# power-management.net
KiCad netlist of a schematic drawn in Altium Designer
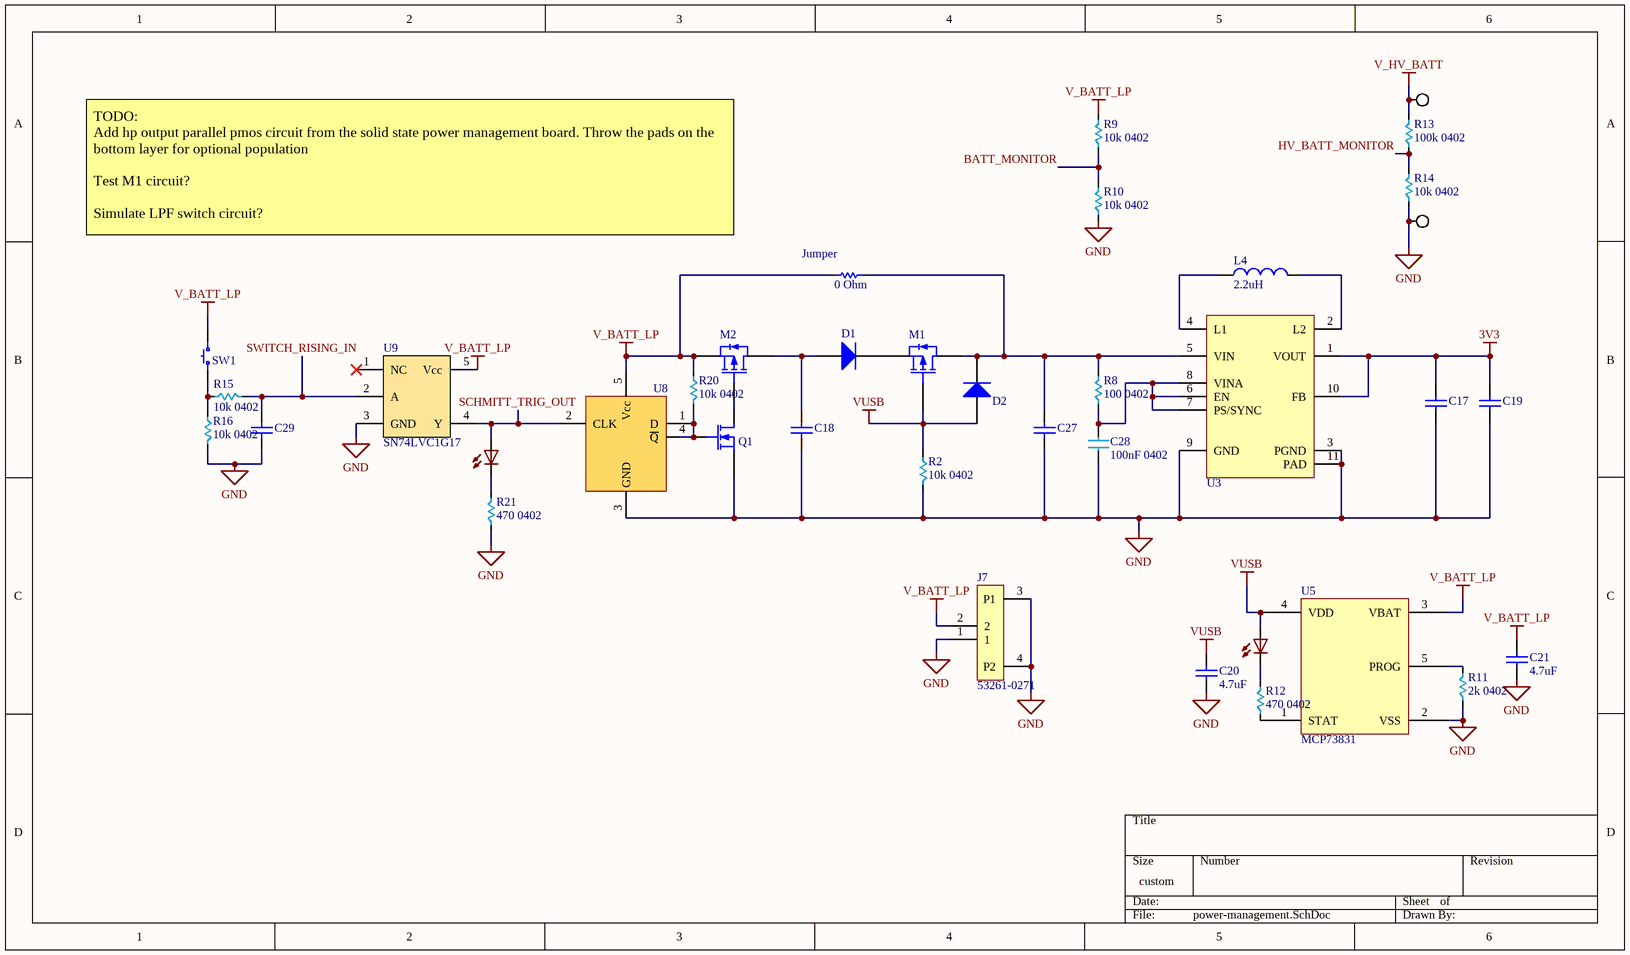
[diagram p0: power-management.SchDoc]

(export (version "E")
  (design (tool "Eeschema 10.0.6"))
  (components
    (comp (ref "0 Ohm")
      (value "Jumper")
      (footprint "0805-1")
      (fields
        (field (name "MANUFACTURER") "Panasonic")
        (field (name "MANUFACTURER PART NUMBER") "ERJ-6LWJR007V")
        (field (name "TOLERANCE") "5%")
      )
      (libsource (lib "robot-cortex") (part "R-0-0805"))
    )
    (comp (ref "C17")
      (value "10uF 0603")
      (footprint "C0603")
      (libsource (lib "robot-cortex") (part "C-10.0uF-0603"))
    )
    (comp (ref "C18")
      (value "10uF 0603")
      (footprint "C0603")
      (libsource (lib "robot-cortex") (part "C-10.0uF-0603"))
    )
    (comp (ref "C19")
      (value "10uF 0603")
      (footprint "C0603")
      (libsource (lib "robot-cortex") (part "C-10.0uF-0603"))
    )
    (comp (ref "C20")
      (value "4.7uF")
      (footprint "C0603")
      (description "4.7uF 0603")
      (fields
        (field (name "MANUFACTURER") "Samsung")
        (field (name "MANUFACTURER PART NUMBER") "CL05F104ZO5NNNC")
        (field (name "PUBLISHER") "Altium Limited")
      )
      (libsource (lib "robot-cortex") (part "C-4.7uF-0603"))
    )
    (comp (ref "C21")
      (value "4.7uF")
      (footprint "C0603")
      (description "4.7uF 0603")
      (fields
        (field (name "MANUFACTURER") "Samsung")
        (field (name "MANUFACTURER PART NUMBER") "CL05F104ZO5NNNC")
        (field (name "PUBLISHER") "Altium Limited")
      )
      (libsource (lib "robot-cortex") (part "C-4.7uF-0603"))
    )
    (comp (ref "C27")
      (value "10uF 0603")
      (footprint "C0603")
      (libsource (lib "robot-cortex") (part "C-10.0uF-0603"))
    )
    (comp (ref "C28") (value "100nF 0402") (footprint "C0402") (libsource (lib "RLC") (part "C0402-100nF")))
    (comp (ref "C29")
      (value "10uF 0603")
      (footprint "C0603")
      (libsource (lib "robot-cortex") (part "C-10.0uF-0603"))
    )
    (comp (ref "D1")
      (value "NSR0530HT1G")
      (footprint "SOD-323")
      (description "DIODE SCHOTTKY 30V 500MA SOD323")
      (fields (field (name "MANUFACTURER") "ON Semiconductor"))
      (libsource (lib "robot-cortex") (part "NSR0530HT1G"))
    )
    (comp (ref "D2")
      (value "NSR0530HT1G")
      (footprint "SOD-323")
      (description "DIODE SCHOTTKY 30V 500MA SOD323")
      (fields (field (name "MANUFACTURER") "ON Semiconductor"))
      (libsource (lib "robot-cortex") (part "NSR0530HT1G"))
    )
    (comp (ref "J7")
      (value "53261-0271")
      (footprint "0532610271")
      (description "Headers & Wire Housings 1.25MM HDR 2 CKT Right-Angle")
      (fields (field (name "MANUFACTURER") "Molex"))
      (libsource (lib "robot-cortex") (part "53261-0271"))
    )
    (comp (ref "J18")
      (value "PAD-SINGLE")
      (footprint "PAD-SINGLE")
      (description "Single Thru Hole Pad")
      (libsource (lib "robot-cortex") (part "PAD-SINGLE"))
    )
    (comp (ref "J19")
      (value "PAD-SINGLE")
      (footprint "PAD-SINGLE")
      (description "Single Thru Hole Pad")
      (libsource (lib "robot-cortex") (part "PAD-SINGLE"))
    )
    (comp (ref "L4")
      (value "2.2uH")
      (footprint "L1210")
      (description "2.2uH 1210")
      (libsource (lib "robot-cortex") (part "DFE322520FD-2R2M=P2"))
    )
    (comp (ref "LED3")
      (value "LED WHITE 0603")
      (footprint "LED_0603")
      (description "LED   Source: http://www.osram.convergy.de   Source: www.luxeon.com   Source: www.kingbright.com")
      (fields
        (field (name "MANUFACTURER") "Dialight")
        (field (name "MANUFACTURER PART NUMBER") "5988070107F")
      )
      (libsource (lib "robot-cortex") (part "LED_ESML0603"))
    )
    (comp (ref "LED4")
      (value "LED WHITE 0603")
      (footprint "LED_0603")
      (description "LED   Source: http://www.osram.convergy.de   Source: www.luxeon.com   Source: www.kingbright.com")
      (fields
        (field (name "MANUFACTURER") "Dialight")
        (field (name "MANUFACTURER PART NUMBER") "5988070107F")
      )
      (libsource (lib "robot-cortex") (part "LED_ESML0603"))
    )
    (comp (ref "M1")
      (value "csd25402q3a")
      (footprint "SON65P330X90-8N")
      (libsource (lib "robot-cortex") (part "CSD25402Q3A"))
    )
    (comp (ref "M2")
      (value "csd25402q3a")
      (footprint "SON65P330X90-8N")
      (libsource (lib "robot-cortex") (part "CSD25402Q3A"))
    )
    (comp (ref "Q1")
      (value "n-mos low power")
      (footprint "SOT-23-3")
      (fields
        (field (name "MANUFACTURER") "ON Semiconductor / Fairchild")
        (field (name "MANUFACTURER PART NUMBER") "NDS351N")
      )
      (libsource (lib "robot-cortex") (part "NDS351N"))
    )
    (comp (ref "R2")
      (value "10k 0402")
      (footprint "R0402")
      (libsource (lib "robot-cortex") (part "R-10k-0402"))
    )
    (comp (ref "R8")
      (value "100 0402")
      (footprint "R0402")
      (libsource (lib "robot-cortex") (part "R-100-0402"))
    )
    (comp (ref "R9")
      (value "10k 0402")
      (footprint "R0402")
      (libsource (lib "robot-cortex") (part "R-10k-0402"))
    )
    (comp (ref "R10")
      (value "10k 0402")
      (footprint "R0402")
      (libsource (lib "robot-cortex") (part "R-10k-0402"))
    )
    (comp (ref "R11")
      (value "2k 0402")
      (footprint "R0402")
      (libsource (lib "robot-cortex") (part "R-2k-0402"))
    )
    (comp (ref "R12")
      (value "470 0402")
      (footprint "R0402")
      (fields
        (field (name "MANUFACTURER") "Yageo")
        (field (name "MANUFACTURER PART NUMBER") "RC0402JR-07470RL")
        (field (name "TOLERANCE") "5%")
      )
      (libsource (lib "robot-cortex") (part "R-470-0402"))
    )
    (comp (ref "R13")
      (value "100k 0402")
      (footprint "R0402")
      (libsource (lib "robot-cortex") (part "R-100k-0402"))
    )
    (comp (ref "R14")
      (value "10k 0402")
      (footprint "R0402")
      (libsource (lib "robot-cortex") (part "R-10k-0402"))
    )
    (comp (ref "R15")
      (value "10k 0402")
      (footprint "R0402")
      (libsource (lib "robot-cortex") (part "R-10k-0402"))
    )
    (comp (ref "R16")
      (value "10k 0402")
      (footprint "R0402")
      (libsource (lib "robot-cortex") (part "R-10k-0402"))
    )
    (comp (ref "R20")
      (value "10k 0402")
      (footprint "R0402")
      (libsource (lib "robot-cortex") (part "R-10k-0402"))
    )
    (comp (ref "R21")
      (value "470 0402")
      (footprint "R0402")
      (fields
        (field (name "MANUFACTURER") "Yageo")
        (field (name "MANUFACTURER PART NUMBER") "RC0402JR-07470RL")
        (field (name "TOLERANCE") "5%")
      )
      (libsource (lib "robot-cortex") (part "R-470-0402"))
    )
    (comp (ref "SW1")
      (value "EVQ-P7A01P")
      (footprint "EVQ-P7A01P")
      (description "SWITCH TACTILE SPST-NO 50MA 32V")
      (fields (field (name "MANUFACTURER") "ITT C&K") (field (name "MANUFACTURER PART NUMBER") "KMR742NGLFS"))
      (libsource (lib "robot-cortex") (part "EVQ-P7A01P"))
    )
    (comp (ref "U3")
      (value "TPS63001DRCR")
      (footprint "DRC0010J")
      (libsource (lib "robot-cortex") (part "TPS63001DRCR"))
    )
    (comp (ref "U5")
      (value "MCP73831")
      (footprint "SOT-23-5")
      (libsource (lib "robot-cortex") (part "MCP73831"))
    )
    (comp (ref "U8")
      (value "SN74LVC1G80DCK")
      (footprint "DCK-SC70-TI")
      (description "Flip Flop Inverted Output")
      (libsource (lib "robot-cortex") (part "SN74LVC1G80DCK"))
    )
    (comp (ref "U9")
      (value "SN74LVC1G17")
      (footprint "DBV-SOT-23")
      (description "TEXAS INSTRUMENTS - SN74LVC1G17DBVR - Buffer, 74LVC1G17, 1.65 V to 5.5 V, SOT-23-5")
      (fields
        (field (name "MANUFACTURER") "Texas Instruments")
        (field (name "MANUFACTURER PART NUMBER") "SN74LVC1G17DBVR")
      )
      (libsource (lib "robot-cortex") (part "SN74LVC1G17"))
    )
  )
  (nets
    (net (code "1") (name "/BATT_MONITOR") (class "Default")
      (node (ref "R10") (pin "1") (pinfunction "1_1") (pintype "passive"))
      (node (ref "R9") (pin "2") (pinfunction "2_2") (pintype "passive"))
    )
    (net (code "2") (name "/HV_BATT_MONITOR") (class "Default")
      (node (ref "R13") (pin "2") (pinfunction "2_2") (pintype "passive"))
      (node (ref "R14") (pin "1") (pinfunction "1_1") (pintype "passive"))
    )
    (net (code "3") (name "/SCHMITT_TRIG_OUT") (class "Default")
      (node (ref "LED4") (pin "A") (pinfunction "A_A") (pintype "passive"))
      (node (ref "U8") (pin "2") (pinfunction "CLK_2") (pintype "passive"))
      (node (ref "U9") (pin "4") (pinfunction "Y_4") (pintype "passive"))
    )
    (net (code "4") (name "/SWITCH_RISING_IN") (class "Default")
      (node (ref "C29") (pin "1") (pinfunction "1_1") (pintype "passive"))
      (node (ref "R15") (pin "2") (pinfunction "2_2") (pintype "passive"))
      (node (ref "U9") (pin "2") (pinfunction "A_2") (pintype "passive"))
    )
    (net (code "5") (name "3V3") (class "Default")
      (node (ref "C17") (pin "2") (pinfunction "2_2") (pintype "passive"))
      (node (ref "C19") (pin "2") (pinfunction "2_2") (pintype "passive"))
      (node (ref "U3") (pin "1") (pinfunction "VOUT_1") (pintype "power_in"))
      (node (ref "U3") (pin "10") (pinfunction "FB_10") (pintype "power_in"))
    )
    (net (code "6") (name "GND") (class "Default")
      (node (ref "C17") (pin "1") (pinfunction "1_1") (pintype "passive"))
      (node (ref "C18") (pin "1") (pinfunction "1_1") (pintype "passive"))
      (node (ref "C19") (pin "1") (pinfunction "1_1") (pintype "passive"))
      (node (ref "C20") (pin "1") (pinfunction "1_1") (pintype "passive"))
      (node (ref "C21") (pin "1") (pinfunction "1_1") (pintype "passive"))
      (node (ref "C27") (pin "1") (pinfunction "1_1") (pintype "passive"))
      (node (ref "C28") (pin "2") (pinfunction "2_2") (pintype "passive"))
      (node (ref "C29") (pin "2") (pinfunction "2_2") (pintype "passive"))
      (node (ref "J19") (pin "1") (pinfunction "1_1") (pintype "passive"))
      (node (ref "J7") (pin "1") (pinfunction "1_1") (pintype "power_in"))
      (node (ref "J7") (pin "3") (pinfunction "P1_3") (pintype "power_in"))
      (node (ref "J7") (pin "4") (pinfunction "P2_4") (pintype "power_in"))
      (node (ref "Q1") (pin "2") (pinfunction "S_2") (pintype "passive"))
      (node (ref "R10") (pin "2") (pinfunction "2_2") (pintype "passive"))
      (node (ref "R11") (pin "2") (pinfunction "2_2") (pintype "passive"))
      (node (ref "R14") (pin "2") (pinfunction "2_2") (pintype "passive"))
      (node (ref "R16") (pin "2") (pinfunction "2_2") (pintype "passive"))
      (node (ref "R2") (pin "1") (pinfunction "1_1") (pintype "passive"))
      (node (ref "R21") (pin "2") (pinfunction "2_2") (pintype "passive"))
      (node (ref "U3") (pin "11") (pinfunction "PAD_11") (pintype "power_in"))
      (node (ref "U3") (pin "3") (pinfunction "PGND_3") (pintype "power_in"))
      (node (ref "U3") (pin "9") (pinfunction "GND_9") (pintype "power_in"))
      (node (ref "U5") (pin "2") (pinfunction "VSS_2") (pintype "passive"))
      (node (ref "U8") (pin "3") (pinfunction "GND_3") (pintype "passive"))
      (node (ref "U9") (pin "3") (pinfunction "GND_3") (pintype "passive"))
    )
    (net (code "7") (name "Net-(D1-A)") (class "Default")
      (node (ref "C18") (pin "2") (pinfunction "2_2") (pintype "passive"))
      (node (ref "D1") (pin "1") (pinfunction "A_1") (pintype "passive"))
      (node (ref "M2") (pin "1") (pinfunction "D_1") (pintype "passive"))
    )
    (net (code "8") (name "Net-(D1-K)") (class "Default")
      (node (ref "D1") (pin "2") (pinfunction "K_2") (pintype "passive"))
      (node (ref "M1") (pin "3") (pinfunction "S_3") (pintype "passive"))
    )
    (net (code "9") (name "Net-(D2-K)") (class "Default")
      (node (ref "0 Ohm") (pin "2") (pinfunction "2_2") (pintype "passive"))
      (node (ref "C27") (pin "2") (pinfunction "2_2") (pintype "passive"))
      (node (ref "D2") (pin "2") (pinfunction "K_2") (pintype "passive"))
      (node (ref "M1") (pin "1") (pinfunction "D_1") (pintype "passive"))
      (node (ref "R8") (pin "1") (pinfunction "1_1") (pintype "passive"))
      (node (ref "U3") (pin "5") (pinfunction "VIN_5") (pintype "power_in"))
    )
    (net (code "10") (name "Net-(LED3-PadC)") (class "Default")
      (node (ref "LED3") (pin "C") (pinfunction "C_C") (pintype "passive"))
      (node (ref "R12") (pin "1") (pinfunction "1_1") (pintype "passive"))
    )
    (net (code "11") (name "Net-(LED4-PadC)") (class "Default")
      (node (ref "LED4") (pin "C") (pinfunction "C_C") (pintype "passive"))
      (node (ref "R21") (pin "1") (pinfunction "1_1") (pintype "passive"))
    )
    (net (code "12") (name "Net-(M2-G)") (class "Default")
      (node (ref "M2") (pin "2") (pinfunction "G_2") (pintype "passive"))
      (node (ref "Q1") (pin "3") (pinfunction "D_3") (pintype "passive"))
    )
    (net (code "13") (name "Net-(Q1-G)") (class "Default")
      (node (ref "Q1") (pin "1") (pinfunction "G_1") (pintype "passive"))
      (node (ref "R20") (pin "1") (pinfunction "1_1") (pintype "passive"))
      (node (ref "U8") (pin "1") (pinfunction "D_1") (pintype "passive"))
      (node (ref "U8") (pin "4") (pinfunction "~{Q}_4") (pintype "passive"))
    )
    (net (code "14") (name "Net-(R15-Pad1)") (class "Default")
      (node (ref "R15") (pin "1") (pinfunction "1_1") (pintype "passive"))
      (node (ref "R16") (pin "1") (pinfunction "1_1") (pintype "passive"))
      (node (ref "SW1") (pin "1") (pinfunction "1_1") (pintype "passive"))
    )
    (net (code "15") (name "Net-(U3-EN)") (class "Default")
      (node (ref "C28") (pin "1") (pinfunction "1_1") (pintype "passive"))
      (node (ref "R8") (pin "2") (pinfunction "2_2") (pintype "passive"))
      (node (ref "U3") (pin "6") (pinfunction "EN_6") (pintype "power_in"))
      (node (ref "U3") (pin "7") (pinfunction "PS/SYNC_7") (pintype "power_in"))
      (node (ref "U3") (pin "8") (pinfunction "VINA_8") (pintype "power_in"))
    )
    (net (code "16") (name "Net-(U3-L1)") (class "Default")
      (node (ref "L4") (pin "1") (pinfunction "1_1") (pintype "passive"))
      (node (ref "U3") (pin "4") (pinfunction "L1_4") (pintype "power_in"))
    )
    (net (code "17") (name "Net-(U3-L2)") (class "Default")
      (node (ref "L4") (pin "2") (pinfunction "2_2") (pintype "passive"))
      (node (ref "U3") (pin "2") (pinfunction "L2_2") (pintype "power_in"))
    )
    (net (code "18") (name "Net-(U5-PROG)") (class "Default")
      (node (ref "R11") (pin "1") (pinfunction "1_1") (pintype "passive"))
      (node (ref "U5") (pin "5") (pinfunction "PROG_5") (pintype "passive"))
    )
    (net (code "19") (name "Net-(U5-STAT)") (class "Default")
      (node (ref "R12") (pin "2") (pinfunction "2_2") (pintype "passive"))
      (node (ref "U5") (pin "1") (pinfunction "STAT_1") (pintype "passive"))
    )
    (net (code "20") (name "VUSB") (class "Default")
      (node (ref "C20") (pin "2") (pinfunction "2_2") (pintype "passive"))
      (node (ref "D2") (pin "1") (pinfunction "A_1") (pintype "passive"))
      (node (ref "LED3") (pin "A") (pinfunction "A_A") (pintype "passive"))
      (node (ref "M1") (pin "2") (pinfunction "G_2") (pintype "passive"))
      (node (ref "R2") (pin "2") (pinfunction "2_2") (pintype "passive"))
      (node (ref "U5") (pin "4") (pinfunction "VDD_4") (pintype "passive"))
    )
    (net (code "21") (name "V_BATT_LP") (class "Default")
      (node (ref "0 Ohm") (pin "1") (pinfunction "1_1") (pintype "passive"))
      (node (ref "C21") (pin "2") (pinfunction "2_2") (pintype "passive"))
      (node (ref "J7") (pin "2") (pinfunction "2_2") (pintype "power_in"))
      (node (ref "M2") (pin "3") (pinfunction "S_3") (pintype "passive"))
      (node (ref "R20") (pin "2") (pinfunction "2_2") (pintype "passive"))
      (node (ref "R9") (pin "1") (pinfunction "1_1") (pintype "passive"))
      (node (ref "SW1") (pin "2") (pinfunction "2_2") (pintype "passive"))
      (node (ref "U5") (pin "3") (pinfunction "VBAT_3") (pintype "passive"))
      (node (ref "U8") (pin "5") (pinfunction "Vcc_5") (pintype "passive"))
      (node (ref "U9") (pin "5") (pinfunction "Vcc_5") (pintype "passive"))
    )
    (net (code "22") (name "V_HV_BATT") (class "Default")
      (node (ref "J18") (pin "1") (pinfunction "1_1") (pintype "passive"))
      (node (ref "R13") (pin "1") (pinfunction "1_1") (pintype "passive"))
    )
    (net (code "23") (name "unconnected-(U9-NC-Pad1)") (class "Default")
      (node (ref "U9") (pin "1") (pinfunction "NC_1") (pintype "passive+no_connect"))
    )
  )
)
